# RGB_LEDs.net
KiCad netlist of a schematic drawn in Altium Designer
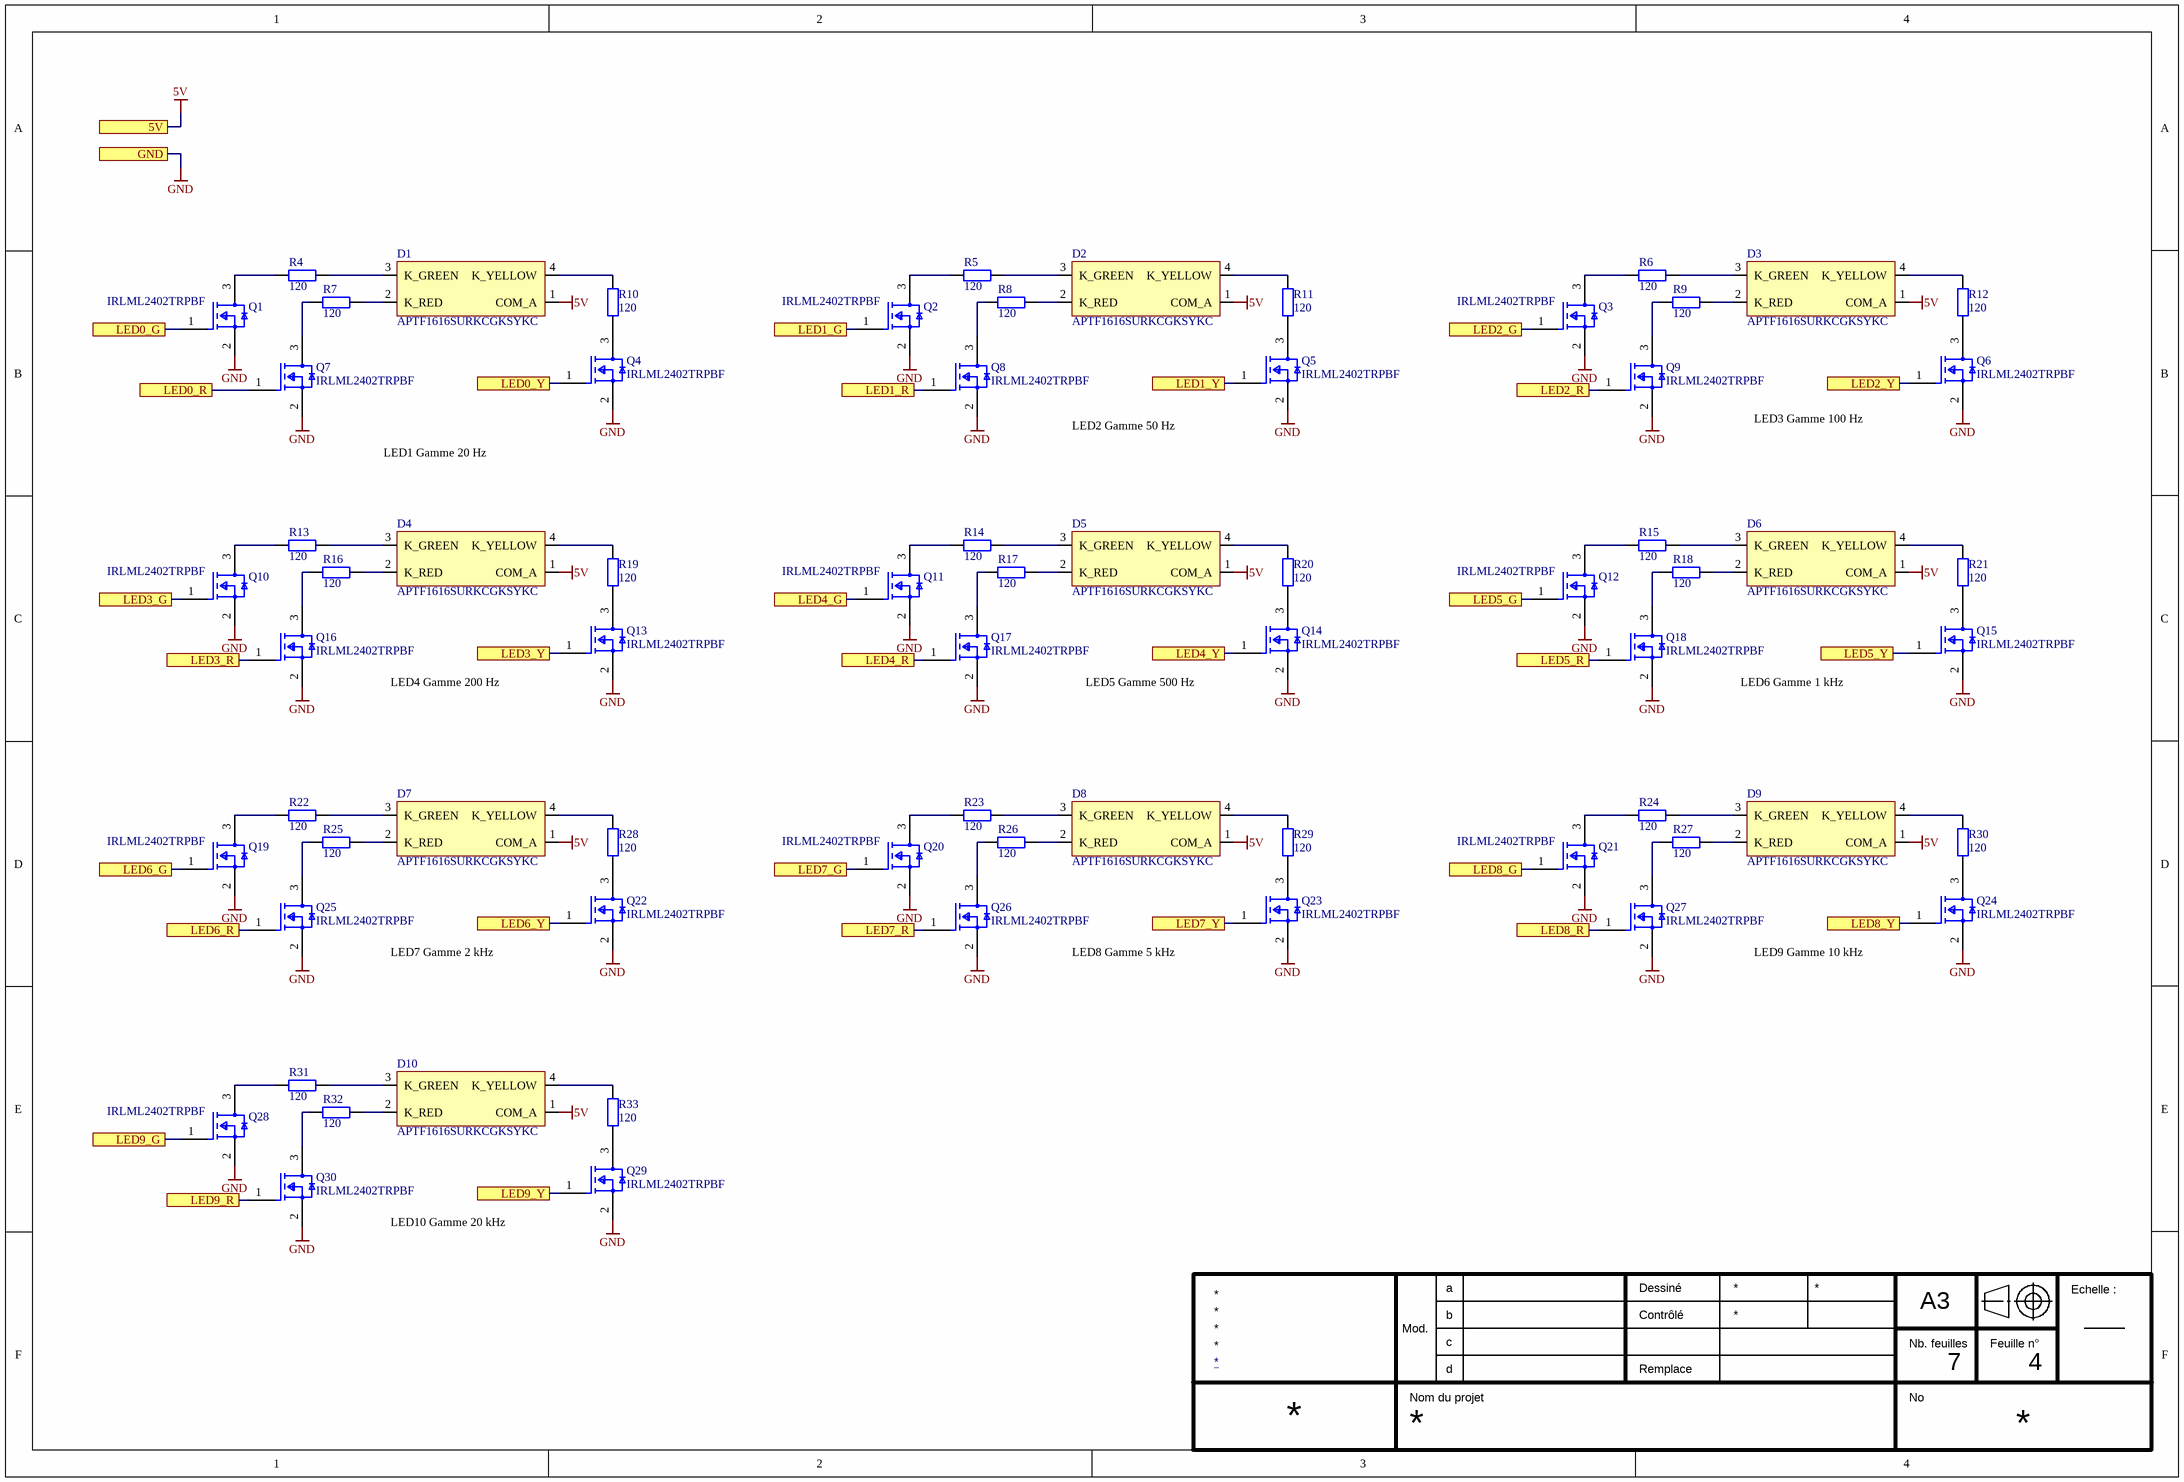
[diagram p0: RGB_LEDs.SchDoc]

(export (version "E")
  (design (tool "Eeschema 10.0.6"))
  (components
    (comp (ref "D1")
      (value "APTF1616SURKCGKSYKC")
      (footprint "APTF1616SURKCGKSYKC")
      (fields (field (name "MOUSER PART NUMBER") "604-APTF1616KCGKSYKC"))
      (libsource (lib "2225B_VumetreFrequenciel") (part "APTF1616SURKCGKSYKC"))
    )
    (comp (ref "D2")
      (value "APTF1616SURKCGKSYKC")
      (footprint "APTF1616SURKCGKSYKC")
      (fields (field (name "MOUSER PART NUMBER") "604-APTF1616KCGKSYKC"))
      (libsource (lib "2225B_VumetreFrequenciel") (part "APTF1616SURKCGKSYKC"))
    )
    (comp (ref "D3")
      (value "APTF1616SURKCGKSYKC")
      (footprint "APTF1616SURKCGKSYKC")
      (fields (field (name "MOUSER PART NUMBER") "604-APTF1616KCGKSYKC"))
      (libsource (lib "2225B_VumetreFrequenciel") (part "APTF1616SURKCGKSYKC"))
    )
    (comp (ref "D4")
      (value "APTF1616SURKCGKSYKC")
      (footprint "APTF1616SURKCGKSYKC")
      (fields (field (name "MOUSER PART NUMBER") "604-APTF1616KCGKSYKC"))
      (libsource (lib "2225B_VumetreFrequenciel") (part "APTF1616SURKCGKSYKC"))
    )
    (comp (ref "D5")
      (value "APTF1616SURKCGKSYKC")
      (footprint "APTF1616SURKCGKSYKC")
      (fields (field (name "MOUSER PART NUMBER") "604-APTF1616KCGKSYKC"))
      (libsource (lib "2225B_VumetreFrequenciel") (part "APTF1616SURKCGKSYKC"))
    )
    (comp (ref "D6")
      (value "APTF1616SURKCGKSYKC")
      (footprint "APTF1616SURKCGKSYKC")
      (fields (field (name "MOUSER PART NUMBER") "604-APTF1616KCGKSYKC"))
      (libsource (lib "2225B_VumetreFrequenciel") (part "APTF1616SURKCGKSYKC"))
    )
    (comp (ref "D7")
      (value "APTF1616SURKCGKSYKC")
      (footprint "APTF1616SURKCGKSYKC")
      (fields (field (name "MOUSER PART NUMBER") "604-APTF1616KCGKSYKC"))
      (libsource (lib "2225B_VumetreFrequenciel") (part "APTF1616SURKCGKSYKC"))
    )
    (comp (ref "D8")
      (value "APTF1616SURKCGKSYKC")
      (footprint "APTF1616SURKCGKSYKC")
      (fields (field (name "MOUSER PART NUMBER") "604-APTF1616KCGKSYKC"))
      (libsource (lib "2225B_VumetreFrequenciel") (part "APTF1616SURKCGKSYKC"))
    )
    (comp (ref "D9")
      (value "APTF1616SURKCGKSYKC")
      (footprint "APTF1616SURKCGKSYKC")
      (fields (field (name "MOUSER PART NUMBER") "604-APTF1616KCGKSYKC"))
      (libsource (lib "2225B_VumetreFrequenciel") (part "APTF1616SURKCGKSYKC"))
    )
    (comp (ref "D10")
      (value "APTF1616SURKCGKSYKC")
      (footprint "APTF1616SURKCGKSYKC")
      (fields (field (name "MOUSER PART NUMBER") "604-APTF1616KCGKSYKC"))
      (libsource (lib "2225B_VumetreFrequenciel") (part "APTF1616SURKCGKSYKC"))
    )
    (comp (ref "Q1")
      (value "IRLML2402TRPBF")
      (footprint "FP-Micro3-IPC_B")
      (description "MOSFET N-CH 20V 1.2A SOT-23")
      (libsource (lib "Altium Content Vault") (part "0a9ea7c96deaaede766a5b531c28de0"))
    )
    (comp (ref "Q2")
      (value "IRLML2402TRPBF")
      (footprint "FP-Micro3-IPC_B")
      (description "MOSFET N-CH 20V 1.2A SOT-23")
      (libsource (lib "Altium Content Vault") (part "0a9ea7c96deaaede766a5b531c28de0"))
    )
    (comp (ref "Q3")
      (value "IRLML2402TRPBF")
      (footprint "FP-Micro3-IPC_B")
      (description "MOSFET N-CH 20V 1.2A SOT-23")
      (libsource (lib "Altium Content Vault") (part "0a9ea7c96deaaede766a5b531c28de0"))
    )
    (comp (ref "Q4")
      (value "IRLML2402TRPBF")
      (footprint "FP-Micro3-IPC_B")
      (description "MOSFET N-CH 20V 1.2A SOT-23")
      (libsource (lib "Altium Content Vault") (part "0a9ea7c96deaaede766a5b531c28de0"))
    )
    (comp (ref "Q5")
      (value "IRLML2402TRPBF")
      (footprint "FP-Micro3-IPC_B")
      (description "MOSFET N-CH 20V 1.2A SOT-23")
      (libsource (lib "Altium Content Vault") (part "0a9ea7c96deaaede766a5b531c28de0"))
    )
    (comp (ref "Q6")
      (value "IRLML2402TRPBF")
      (footprint "FP-Micro3-IPC_B")
      (description "MOSFET N-CH 20V 1.2A SOT-23")
      (libsource (lib "Altium Content Vault") (part "0a9ea7c96deaaede766a5b531c28de0"))
    )
    (comp (ref "Q7")
      (value "IRLML2402TRPBF")
      (footprint "FP-Micro3-IPC_B")
      (description "MOSFET N-CH 20V 1.2A SOT-23")
      (libsource (lib "Altium Content Vault") (part "0a9ea7c96deaaede766a5b531c28de0"))
    )
    (comp (ref "Q8")
      (value "IRLML2402TRPBF")
      (footprint "FP-Micro3-IPC_B")
      (description "MOSFET N-CH 20V 1.2A SOT-23")
      (libsource (lib "Altium Content Vault") (part "0a9ea7c96deaaede766a5b531c28de0"))
    )
    (comp (ref "Q9")
      (value "IRLML2402TRPBF")
      (footprint "FP-Micro3-IPC_B")
      (description "MOSFET N-CH 20V 1.2A SOT-23")
      (libsource (lib "Altium Content Vault") (part "0a9ea7c96deaaede766a5b531c28de0"))
    )
    (comp (ref "Q10")
      (value "IRLML2402TRPBF")
      (footprint "FP-Micro3-IPC_B")
      (description "MOSFET N-CH 20V 1.2A SOT-23")
      (libsource (lib "Altium Content Vault") (part "0a9ea7c96deaaede766a5b531c28de0"))
    )
    (comp (ref "Q11")
      (value "IRLML2402TRPBF")
      (footprint "FP-Micro3-IPC_B")
      (description "MOSFET N-CH 20V 1.2A SOT-23")
      (libsource (lib "Altium Content Vault") (part "0a9ea7c96deaaede766a5b531c28de0"))
    )
    (comp (ref "Q12")
      (value "IRLML2402TRPBF")
      (footprint "FP-Micro3-IPC_B")
      (description "MOSFET N-CH 20V 1.2A SOT-23")
      (libsource (lib "Altium Content Vault") (part "0a9ea7c96deaaede766a5b531c28de0"))
    )
    (comp (ref "Q13")
      (value "IRLML2402TRPBF")
      (footprint "FP-Micro3-IPC_B")
      (description "MOSFET N-CH 20V 1.2A SOT-23")
      (libsource (lib "Altium Content Vault") (part "0a9ea7c96deaaede766a5b531c28de0"))
    )
    (comp (ref "Q14")
      (value "IRLML2402TRPBF")
      (footprint "FP-Micro3-IPC_B")
      (description "MOSFET N-CH 20V 1.2A SOT-23")
      (libsource (lib "Altium Content Vault") (part "0a9ea7c96deaaede766a5b531c28de0"))
    )
    (comp (ref "Q15")
      (value "IRLML2402TRPBF")
      (footprint "FP-Micro3-IPC_B")
      (description "MOSFET N-CH 20V 1.2A SOT-23")
      (libsource (lib "Altium Content Vault") (part "0a9ea7c96deaaede766a5b531c28de0"))
    )
    (comp (ref "Q16")
      (value "IRLML2402TRPBF")
      (footprint "FP-Micro3-IPC_B")
      (description "MOSFET N-CH 20V 1.2A SOT-23")
      (libsource (lib "Altium Content Vault") (part "0a9ea7c96deaaede766a5b531c28de0"))
    )
    (comp (ref "Q17")
      (value "IRLML2402TRPBF")
      (footprint "FP-Micro3-IPC_B")
      (description "MOSFET N-CH 20V 1.2A SOT-23")
      (libsource (lib "Altium Content Vault") (part "0a9ea7c96deaaede766a5b531c28de0"))
    )
    (comp (ref "Q18")
      (value "IRLML2402TRPBF")
      (footprint "FP-Micro3-IPC_B")
      (description "MOSFET N-CH 20V 1.2A SOT-23")
      (libsource (lib "Altium Content Vault") (part "0a9ea7c96deaaede766a5b531c28de0"))
    )
    (comp (ref "Q19")
      (value "IRLML2402TRPBF")
      (footprint "FP-Micro3-IPC_B")
      (description "MOSFET N-CH 20V 1.2A SOT-23")
      (libsource (lib "Altium Content Vault") (part "0a9ea7c96deaaede766a5b531c28de0"))
    )
    (comp (ref "Q20")
      (value "IRLML2402TRPBF")
      (footprint "FP-Micro3-IPC_B")
      (description "MOSFET N-CH 20V 1.2A SOT-23")
      (libsource (lib "Altium Content Vault") (part "0a9ea7c96deaaede766a5b531c28de0"))
    )
    (comp (ref "Q21")
      (value "IRLML2402TRPBF")
      (footprint "FP-Micro3-IPC_B")
      (description "MOSFET N-CH 20V 1.2A SOT-23")
      (libsource (lib "Altium Content Vault") (part "0a9ea7c96deaaede766a5b531c28de0"))
    )
    (comp (ref "Q22")
      (value "IRLML2402TRPBF")
      (footprint "FP-Micro3-IPC_B")
      (description "MOSFET N-CH 20V 1.2A SOT-23")
      (libsource (lib "Altium Content Vault") (part "0a9ea7c96deaaede766a5b531c28de0"))
    )
    (comp (ref "Q23")
      (value "IRLML2402TRPBF")
      (footprint "FP-Micro3-IPC_B")
      (description "MOSFET N-CH 20V 1.2A SOT-23")
      (libsource (lib "Altium Content Vault") (part "0a9ea7c96deaaede766a5b531c28de0"))
    )
    (comp (ref "Q24")
      (value "IRLML2402TRPBF")
      (footprint "FP-Micro3-IPC_B")
      (description "MOSFET N-CH 20V 1.2A SOT-23")
      (libsource (lib "Altium Content Vault") (part "0a9ea7c96deaaede766a5b531c28de0"))
    )
    (comp (ref "Q25")
      (value "IRLML2402TRPBF")
      (footprint "FP-Micro3-IPC_B")
      (description "MOSFET N-CH 20V 1.2A SOT-23")
      (libsource (lib "Altium Content Vault") (part "0a9ea7c96deaaede766a5b531c28de0"))
    )
    (comp (ref "Q26")
      (value "IRLML2402TRPBF")
      (footprint "FP-Micro3-IPC_B")
      (description "MOSFET N-CH 20V 1.2A SOT-23")
      (libsource (lib "Altium Content Vault") (part "0a9ea7c96deaaede766a5b531c28de0"))
    )
    (comp (ref "Q27")
      (value "IRLML2402TRPBF")
      (footprint "FP-Micro3-IPC_B")
      (description "MOSFET N-CH 20V 1.2A SOT-23")
      (libsource (lib "Altium Content Vault") (part "0a9ea7c96deaaede766a5b531c28de0"))
    )
    (comp (ref "Q28")
      (value "IRLML2402TRPBF")
      (footprint "FP-Micro3-IPC_B")
      (description "MOSFET N-CH 20V 1.2A SOT-23")
      (libsource (lib "Altium Content Vault") (part "0a9ea7c96deaaede766a5b531c28de0"))
    )
    (comp (ref "Q29")
      (value "IRLML2402TRPBF")
      (footprint "FP-Micro3-IPC_B")
      (description "MOSFET N-CH 20V 1.2A SOT-23")
      (libsource (lib "Altium Content Vault") (part "0a9ea7c96deaaede766a5b531c28de0"))
    )
    (comp (ref "Q30")
      (value "IRLML2402TRPBF")
      (footprint "FP-Micro3-IPC_B")
      (description "MOSFET N-CH 20V 1.2A SOT-23")
      (libsource (lib "Altium Content Vault") (part "0a9ea7c96deaaede766a5b531c28de0"))
    )
    (comp (ref "R4")
      (value "120")
      (footprint "RESC2012X06M")
      (description "Resistor")
      (fields (field (name "PUBLISHER") "Altium Limited"))
      (libsource (lib "") (part "Res2_1"))
    )
    (comp (ref "R5")
      (value "120")
      (footprint "RESC2012X06M")
      (description "Resistor")
      (fields (field (name "PUBLISHER") "Altium Limited"))
      (libsource (lib "") (part "Res2_1"))
    )
    (comp (ref "R6")
      (value "120")
      (footprint "RESC2012X06M")
      (description "Resistor")
      (fields (field (name "PUBLISHER") "Altium Limited"))
      (libsource (lib "") (part "Res2_1"))
    )
    (comp (ref "R7")
      (value "120")
      (footprint "RESC2012X06M")
      (description "Resistor")
      (fields (field (name "PUBLISHER") "Altium Limited"))
      (libsource (lib "") (part "Res2_1"))
    )
    (comp (ref "R8")
      (value "120")
      (footprint "RESC2012X06M")
      (description "Resistor")
      (fields (field (name "PUBLISHER") "Altium Limited"))
      (libsource (lib "") (part "Res2_1"))
    )
    (comp (ref "R9")
      (value "120")
      (footprint "RESC2012X06M")
      (description "Resistor")
      (fields (field (name "PUBLISHER") "Altium Limited"))
      (libsource (lib "") (part "Res2_1"))
    )
    (comp (ref "R10")
      (value "120")
      (footprint "RESC2012X06M")
      (description "Resistor")
      (fields (field (name "PUBLISHER") "Altium Limited"))
      (libsource (lib "Miscellaneous Devices") (part "Res2"))
    )
    (comp (ref "R11")
      (value "120")
      (footprint "RESC2012X06M")
      (description "Resistor")
      (fields (field (name "PUBLISHER") "Altium Limited"))
      (libsource (lib "Miscellaneous Devices") (part "Res2"))
    )
    (comp (ref "R12")
      (value "120")
      (footprint "RESC2012X06M")
      (description "Resistor")
      (fields (field (name "PUBLISHER") "Altium Limited"))
      (libsource (lib "Miscellaneous Devices") (part "Res2"))
    )
    (comp (ref "R13")
      (value "120")
      (footprint "RESC2012X06M")
      (description "Resistor")
      (fields (field (name "PUBLISHER") "Altium Limited"))
      (libsource (lib "") (part "Res2_1"))
    )
    (comp (ref "R14")
      (value "120")
      (footprint "RESC2012X06M")
      (description "Resistor")
      (fields (field (name "PUBLISHER") "Altium Limited"))
      (libsource (lib "") (part "Res2_1"))
    )
    (comp (ref "R15")
      (value "120")
      (footprint "RESC2012X06M")
      (description "Resistor")
      (fields (field (name "PUBLISHER") "Altium Limited"))
      (libsource (lib "") (part "Res2_1"))
    )
    (comp (ref "R16")
      (value "120")
      (footprint "RESC2012X06M")
      (description "Resistor")
      (fields (field (name "PUBLISHER") "Altium Limited"))
      (libsource (lib "") (part "Res2_1"))
    )
    (comp (ref "R17")
      (value "120")
      (footprint "RESC2012X06M")
      (description "Resistor")
      (fields (field (name "PUBLISHER") "Altium Limited"))
      (libsource (lib "") (part "Res2_1"))
    )
    (comp (ref "R18")
      (value "120")
      (footprint "RESC2012X06M")
      (description "Resistor")
      (fields (field (name "PUBLISHER") "Altium Limited"))
      (libsource (lib "") (part "Res2_1"))
    )
    (comp (ref "R19")
      (value "120")
      (footprint "RESC2012X06M")
      (description "Resistor")
      (fields (field (name "PUBLISHER") "Altium Limited"))
      (libsource (lib "Miscellaneous Devices") (part "Res2"))
    )
    (comp (ref "R20")
      (value "120")
      (footprint "RESC2012X06M")
      (description "Resistor")
      (fields (field (name "PUBLISHER") "Altium Limited"))
      (libsource (lib "Miscellaneous Devices") (part "Res2"))
    )
    (comp (ref "R21")
      (value "120")
      (footprint "RESC2012X06M")
      (description "Resistor")
      (fields (field (name "PUBLISHER") "Altium Limited"))
      (libsource (lib "Miscellaneous Devices") (part "Res2"))
    )
    (comp (ref "R22")
      (value "120")
      (footprint "RESC2012X06M")
      (description "Resistor")
      (fields (field (name "PUBLISHER") "Altium Limited"))
      (libsource (lib "") (part "Res2_1"))
    )
    (comp (ref "R23")
      (value "120")
      (footprint "RESC2012X06M")
      (description "Resistor")
      (fields (field (name "PUBLISHER") "Altium Limited"))
      (libsource (lib "") (part "Res2_1"))
    )
    (comp (ref "R24")
      (value "120")
      (footprint "RESC2012X06M")
      (description "Resistor")
      (fields (field (name "PUBLISHER") "Altium Limited"))
      (libsource (lib "") (part "Res2_1"))
    )
    (comp (ref "R25")
      (value "120")
      (footprint "RESC2012X06M")
      (description "Resistor")
      (fields (field (name "PUBLISHER") "Altium Limited"))
      (libsource (lib "") (part "Res2_1"))
    )
    (comp (ref "R26")
      (value "120")
      (footprint "RESC2012X06M")
      (description "Resistor")
      (fields (field (name "PUBLISHER") "Altium Limited"))
      (libsource (lib "") (part "Res2_1"))
    )
    (comp (ref "R27")
      (value "120")
      (footprint "RESC2012X06M")
      (description "Resistor")
      (fields (field (name "PUBLISHER") "Altium Limited"))
      (libsource (lib "") (part "Res2_1"))
    )
    (comp (ref "R28")
      (value "120")
      (footprint "RESC2012X06M")
      (description "Resistor")
      (fields (field (name "PUBLISHER") "Altium Limited"))
      (libsource (lib "Miscellaneous Devices") (part "Res2"))
    )
    (comp (ref "R29")
      (value "120")
      (footprint "RESC2012X06M")
      (description "Resistor")
      (fields (field (name "PUBLISHER") "Altium Limited"))
      (libsource (lib "Miscellaneous Devices") (part "Res2"))
    )
    (comp (ref "R30")
      (value "120")
      (footprint "RESC2012X06M")
      (description "Resistor")
      (fields (field (name "PUBLISHER") "Altium Limited"))
      (libsource (lib "Miscellaneous Devices") (part "Res2"))
    )
    (comp (ref "R31")
      (value "120")
      (footprint "RESC2012X06M")
      (description "Resistor")
      (fields (field (name "PUBLISHER") "Altium Limited"))
      (libsource (lib "") (part "Res2_1"))
    )
    (comp (ref "R32")
      (value "120")
      (footprint "RESC2012X06M")
      (description "Resistor")
      (fields (field (name "PUBLISHER") "Altium Limited"))
      (libsource (lib "") (part "Res2_1"))
    )
    (comp (ref "R33")
      (value "120")
      (footprint "RESC2012X06M")
      (description "Resistor")
      (fields (field (name "PUBLISHER") "Altium Limited"))
      (libsource (lib "Miscellaneous Devices") (part "Res2"))
    )
  )
  (nets
    (net (code "1") (name "/LED0_G") (class "Default")
      (node (ref "Q1") (pin "1") (pinfunction "G_1") (pintype "passive"))
    )
    (net (code "2") (name "/LED0_R") (class "Default")
      (node (ref "Q7") (pin "1") (pinfunction "G_1") (pintype "passive"))
    )
    (net (code "3") (name "/LED0_Y") (class "Default")
      (node (ref "Q4") (pin "1") (pinfunction "G_1") (pintype "passive"))
    )
    (net (code "4") (name "/LED1_G") (class "Default")
      (node (ref "Q2") (pin "1") (pinfunction "G_1") (pintype "passive"))
    )
    (net (code "5") (name "/LED1_R") (class "Default")
      (node (ref "Q8") (pin "1") (pinfunction "G_1") (pintype "passive"))
    )
    (net (code "6") (name "/LED1_Y") (class "Default")
      (node (ref "Q5") (pin "1") (pinfunction "G_1") (pintype "passive"))
    )
    (net (code "7") (name "/LED2_G") (class "Default")
      (node (ref "Q3") (pin "1") (pinfunction "G_1") (pintype "passive"))
    )
    (net (code "8") (name "/LED2_R") (class "Default")
      (node (ref "Q9") (pin "1") (pinfunction "G_1") (pintype "passive"))
    )
    (net (code "9") (name "/LED2_Y") (class "Default")
      (node (ref "Q6") (pin "1") (pinfunction "G_1") (pintype "passive"))
    )
    (net (code "10") (name "/LED3_G") (class "Default")
      (node (ref "Q10") (pin "1") (pinfunction "G_1") (pintype "passive"))
    )
    (net (code "11") (name "/LED3_R") (class "Default")
      (node (ref "Q16") (pin "1") (pinfunction "G_1") (pintype "passive"))
    )
    (net (code "12") (name "/LED3_Y") (class "Default")
      (node (ref "Q13") (pin "1") (pinfunction "G_1") (pintype "passive"))
    )
    (net (code "13") (name "/LED4_G") (class "Default")
      (node (ref "Q11") (pin "1") (pinfunction "G_1") (pintype "passive"))
    )
    (net (code "14") (name "/LED4_R") (class "Default")
      (node (ref "Q17") (pin "1") (pinfunction "G_1") (pintype "passive"))
    )
    (net (code "15") (name "/LED4_Y") (class "Default")
      (node (ref "Q14") (pin "1") (pinfunction "G_1") (pintype "passive"))
    )
    (net (code "16") (name "/LED5_G") (class "Default")
      (node (ref "Q12") (pin "1") (pinfunction "G_1") (pintype "passive"))
    )
    (net (code "17") (name "/LED5_R") (class "Default")
      (node (ref "Q18") (pin "1") (pinfunction "G_1") (pintype "passive"))
    )
    (net (code "18") (name "/LED5_Y") (class "Default")
      (node (ref "Q15") (pin "1") (pinfunction "G_1") (pintype "passive"))
    )
    (net (code "19") (name "/LED6_G") (class "Default")
      (node (ref "Q19") (pin "1") (pinfunction "G_1") (pintype "passive"))
    )
    (net (code "20") (name "/LED6_R") (class "Default")
      (node (ref "Q25") (pin "1") (pinfunction "G_1") (pintype "passive"))
    )
    (net (code "21") (name "/LED6_Y") (class "Default")
      (node (ref "Q22") (pin "1") (pinfunction "G_1") (pintype "passive"))
    )
    (net (code "22") (name "/LED7_G") (class "Default")
      (node (ref "Q20") (pin "1") (pinfunction "G_1") (pintype "passive"))
    )
    (net (code "23") (name "/LED7_R") (class "Default")
      (node (ref "Q26") (pin "1") (pinfunction "G_1") (pintype "passive"))
    )
    (net (code "24") (name "/LED7_Y") (class "Default")
      (node (ref "Q23") (pin "1") (pinfunction "G_1") (pintype "passive"))
    )
    (net (code "25") (name "/LED8_G") (class "Default")
      (node (ref "Q21") (pin "1") (pinfunction "G_1") (pintype "passive"))
    )
    (net (code "26") (name "/LED8_R") (class "Default")
      (node (ref "Q27") (pin "1") (pinfunction "G_1") (pintype "passive"))
    )
    (net (code "27") (name "/LED8_Y") (class "Default")
      (node (ref "Q24") (pin "1") (pinfunction "G_1") (pintype "passive"))
    )
    (net (code "28") (name "/LED9_G") (class "Default")
      (node (ref "Q28") (pin "1") (pinfunction "G_1") (pintype "passive"))
    )
    (net (code "29") (name "/LED9_R") (class "Default")
      (node (ref "Q30") (pin "1") (pinfunction "G_1") (pintype "passive"))
    )
    (net (code "30") (name "/LED9_Y") (class "Default")
      (node (ref "Q29") (pin "1") (pinfunction "G_1") (pintype "passive"))
    )
    (net (code "31") (name "5V") (class "Default")
      (node (ref "D1") (pin "1") (pinfunction "COM_A_1") (pintype "passive"))
      (node (ref "D10") (pin "1") (pinfunction "COM_A_1") (pintype "passive"))
      (node (ref "D2") (pin "1") (pinfunction "COM_A_1") (pintype "passive"))
      (node (ref "D3") (pin "1") (pinfunction "COM_A_1") (pintype "passive"))
      (node (ref "D4") (pin "1") (pinfunction "COM_A_1") (pintype "passive"))
      (node (ref "D5") (pin "1") (pinfunction "COM_A_1") (pintype "passive"))
      (node (ref "D6") (pin "1") (pinfunction "COM_A_1") (pintype "passive"))
      (node (ref "D7") (pin "1") (pinfunction "COM_A_1") (pintype "passive"))
      (node (ref "D8") (pin "1") (pinfunction "COM_A_1") (pintype "passive"))
      (node (ref "D9") (pin "1") (pinfunction "COM_A_1") (pintype "passive"))
    )
    (net (code "32") (name "GND") (class "Default")
      (node (ref "Q1") (pin "2") (pinfunction "S_2") (pintype "passive"))
      (node (ref "Q10") (pin "2") (pinfunction "S_2") (pintype "passive"))
      (node (ref "Q11") (pin "2") (pinfunction "S_2") (pintype "passive"))
      (node (ref "Q12") (pin "2") (pinfunction "S_2") (pintype "passive"))
      (node (ref "Q13") (pin "2") (pinfunction "S_2") (pintype "passive"))
      (node (ref "Q14") (pin "2") (pinfunction "S_2") (pintype "passive"))
      (node (ref "Q15") (pin "2") (pinfunction "S_2") (pintype "passive"))
      (node (ref "Q16") (pin "2") (pinfunction "S_2") (pintype "passive"))
      (node (ref "Q17") (pin "2") (pinfunction "S_2") (pintype "passive"))
      (node (ref "Q18") (pin "2") (pinfunction "S_2") (pintype "passive"))
      (node (ref "Q19") (pin "2") (pinfunction "S_2") (pintype "passive"))
      (node (ref "Q2") (pin "2") (pinfunction "S_2") (pintype "passive"))
      (node (ref "Q20") (pin "2") (pinfunction "S_2") (pintype "passive"))
      (node (ref "Q21") (pin "2") (pinfunction "S_2") (pintype "passive"))
      (node (ref "Q22") (pin "2") (pinfunction "S_2") (pintype "passive"))
      (node (ref "Q23") (pin "2") (pinfunction "S_2") (pintype "passive"))
      (node (ref "Q24") (pin "2") (pinfunction "S_2") (pintype "passive"))
      (node (ref "Q25") (pin "2") (pinfunction "S_2") (pintype "passive"))
      (node (ref "Q26") (pin "2") (pinfunction "S_2") (pintype "passive"))
      (node (ref "Q27") (pin "2") (pinfunction "S_2") (pintype "passive"))
      (node (ref "Q28") (pin "2") (pinfunction "S_2") (pintype "passive"))
      (node (ref "Q29") (pin "2") (pinfunction "S_2") (pintype "passive"))
      (node (ref "Q3") (pin "2") (pinfunction "S_2") (pintype "passive"))
      (node (ref "Q30") (pin "2") (pinfunction "S_2") (pintype "passive"))
      (node (ref "Q4") (pin "2") (pinfunction "S_2") (pintype "passive"))
      (node (ref "Q5") (pin "2") (pinfunction "S_2") (pintype "passive"))
      (node (ref "Q6") (pin "2") (pinfunction "S_2") (pintype "passive"))
      (node (ref "Q7") (pin "2") (pinfunction "S_2") (pintype "passive"))
      (node (ref "Q8") (pin "2") (pinfunction "S_2") (pintype "passive"))
      (node (ref "Q9") (pin "2") (pinfunction "S_2") (pintype "passive"))
    )
    (net (code "33") (name "Net-(D1-K_GREEN)") (class "Default")
      (node (ref "D1") (pin "3") (pinfunction "K_GREEN_3") (pintype "passive"))
      (node (ref "R4") (pin "1") (pinfunction "1_1") (pintype "passive"))
    )
    (net (code "34") (name "Net-(D1-K_RED)") (class "Default")
      (node (ref "D1") (pin "2") (pinfunction "K_RED_2") (pintype "passive"))
      (node (ref "R7") (pin "1") (pinfunction "1_1") (pintype "passive"))
    )
    (net (code "35") (name "Net-(D1-K_YELLOW)") (class "Default")
      (node (ref "D1") (pin "4") (pinfunction "K_YELLOW_4") (pintype "passive"))
      (node (ref "R10") (pin "1") (pinfunction "1_1") (pintype "passive"))
    )
    (net (code "36") (name "Net-(D2-K_GREEN)") (class "Default")
      (node (ref "D2") (pin "3") (pinfunction "K_GREEN_3") (pintype "passive"))
      (node (ref "R5") (pin "1") (pinfunction "1_1") (pintype "passive"))
    )
    (net (code "37") (name "Net-(D2-K_RED)") (class "Default")
      (node (ref "D2") (pin "2") (pinfunction "K_RED_2") (pintype "passive"))
      (node (ref "R8") (pin "1") (pinfunction "1_1") (pintype "passive"))
    )
    (net (code "38") (name "Net-(D2-K_YELLOW)") (class "Default")
      (node (ref "D2") (pin "4") (pinfunction "K_YELLOW_4") (pintype "passive"))
      (node (ref "R11") (pin "1") (pinfunction "1_1") (pintype "passive"))
    )
    (net (code "39") (name "Net-(D3-K_GREEN)") (class "Default")
      (node (ref "D3") (pin "3") (pinfunction "K_GREEN_3") (pintype "passive"))
      (node (ref "R6") (pin "1") (pinfunction "1_1") (pintype "passive"))
    )
    (net (code "40") (name "Net-(D3-K_RED)") (class "Default")
      (node (ref "D3") (pin "2") (pinfunction "K_RED_2") (pintype "passive"))
      (node (ref "R9") (pin "1") (pinfunction "1_1") (pintype "passive"))
    )
    (net (code "41") (name "Net-(D3-K_YELLOW)") (class "Default")
      (node (ref "D3") (pin "4") (pinfunction "K_YELLOW_4") (pintype "passive"))
      (node (ref "R12") (pin "1") (pinfunction "1_1") (pintype "passive"))
    )
    (net (code "42") (name "Net-(D4-K_GREEN)") (class "Default")
      (node (ref "D4") (pin "3") (pinfunction "K_GREEN_3") (pintype "passive"))
      (node (ref "R13") (pin "1") (pinfunction "1_1") (pintype "passive"))
    )
    (net (code "43") (name "Net-(D4-K_RED)") (class "Default")
      (node (ref "D4") (pin "2") (pinfunction "K_RED_2") (pintype "passive"))
      (node (ref "R16") (pin "1") (pinfunction "1_1") (pintype "passive"))
    )
    (net (code "44") (name "Net-(D4-K_YELLOW)") (class "Default")
      (node (ref "D4") (pin "4") (pinfunction "K_YELLOW_4") (pintype "passive"))
      (node (ref "R19") (pin "1") (pinfunction "1_1") (pintype "passive"))
    )
    (net (code "45") (name "Net-(D5-K_GREEN)") (class "Default")
      (node (ref "D5") (pin "3") (pinfunction "K_GREEN_3") (pintype "passive"))
      (node (ref "R14") (pin "1") (pinfunction "1_1") (pintype "passive"))
    )
    (net (code "46") (name "Net-(D5-K_RED)") (class "Default")
      (node (ref "D5") (pin "2") (pinfunction "K_RED_2") (pintype "passive"))
      (node (ref "R17") (pin "1") (pinfunction "1_1") (pintype "passive"))
    )
    (net (code "47") (name "Net-(D5-K_YELLOW)") (class "Default")
      (node (ref "D5") (pin "4") (pinfunction "K_YELLOW_4") (pintype "passive"))
      (node (ref "R20") (pin "1") (pinfunction "1_1") (pintype "passive"))
    )
    (net (code "48") (name "Net-(D6-K_GREEN)") (class "Default")
      (node (ref "D6") (pin "3") (pinfunction "K_GREEN_3") (pintype "passive"))
      (node (ref "R15") (pin "1") (pinfunction "1_1") (pintype "passive"))
    )
    (net (code "49") (name "Net-(D6-K_RED)") (class "Default")
      (node (ref "D6") (pin "2") (pinfunction "K_RED_2") (pintype "passive"))
      (node (ref "R18") (pin "1") (pinfunction "1_1") (pintype "passive"))
    )
    (net (code "50") (name "Net-(D6-K_YELLOW)") (class "Default")
      (node (ref "D6") (pin "4") (pinfunction "K_YELLOW_4") (pintype "passive"))
      (node (ref "R21") (pin "1") (pinfunction "1_1") (pintype "passive"))
    )
    (net (code "51") (name "Net-(D7-K_GREEN)") (class "Default")
      (node (ref "D7") (pin "3") (pinfunction "K_GREEN_3") (pintype "passive"))
      (node (ref "R22") (pin "1") (pinfunction "1_1") (pintype "passive"))
    )
    (net (code "52") (name "Net-(D7-K_RED)") (class "Default")
      (node (ref "D7") (pin "2") (pinfunction "K_RED_2") (pintype "passive"))
      (node (ref "R25") (pin "1") (pinfunction "1_1") (pintype "passive"))
    )
    (net (code "53") (name "Net-(D7-K_YELLOW)") (class "Default")
      (node (ref "D7") (pin "4") (pinfunction "K_YELLOW_4") (pintype "passive"))
      (node (ref "R28") (pin "1") (pinfunction "1_1") (pintype "passive"))
    )
    (net (code "54") (name "Net-(D8-K_GREEN)") (class "Default")
      (node (ref "D8") (pin "3") (pinfunction "K_GREEN_3") (pintype "passive"))
      (node (ref "R23") (pin "1") (pinfunction "1_1") (pintype "passive"))
    )
    (net (code "55") (name "Net-(D8-K_RED)") (class "Default")
      (node (ref "D8") (pin "2") (pinfunction "K_RED_2") (pintype "passive"))
      (node (ref "R26") (pin "1") (pinfunction "1_1") (pintype "passive"))
    )
    (net (code "56") (name "Net-(D8-K_YELLOW)") (class "Default")
      (node (ref "D8") (pin "4") (pinfunction "K_YELLOW_4") (pintype "passive"))
      (node (ref "R29") (pin "1") (pinfunction "1_1") (pintype "passive"))
    )
    (net (code "57") (name "Net-(D9-K_GREEN)") (class "Default")
      (node (ref "D9") (pin "3") (pinfunction "K_GREEN_3") (pintype "passive"))
      (node (ref "R24") (pin "1") (pinfunction "1_1") (pintype "passive"))
    )
    (net (code "58") (name "Net-(D9-K_RED)") (class "Default")
      (node (ref "D9") (pin "2") (pinfunction "K_RED_2") (pintype "passive"))
      (node (ref "R27") (pin "1") (pinfunction "1_1") (pintype "passive"))
    )
    (net (code "59") (name "Net-(D9-K_YELLOW)") (class "Default")
      (node (ref "D9") (pin "4") (pinfunction "K_YELLOW_4") (pintype "passive"))
      (node (ref "R30") (pin "1") (pinfunction "1_1") (pintype "passive"))
    )
    (net (code "60") (name "Net-(D10-K_GREEN)") (class "Default")
      (node (ref "D10") (pin "3") (pinfunction "K_GREEN_3") (pintype "passive"))
      (node (ref "R31") (pin "1") (pinfunction "1_1") (pintype "passive"))
    )
    (net (code "61") (name "Net-(D10-K_RED)") (class "Default")
      (node (ref "D10") (pin "2") (pinfunction "K_RED_2") (pintype "passive"))
      (node (ref "R32") (pin "1") (pinfunction "1_1") (pintype "passive"))
    )
    (net (code "62") (name "Net-(D10-K_YELLOW)") (class "Default")
      (node (ref "D10") (pin "4") (pinfunction "K_YELLOW_4") (pintype "passive"))
      (node (ref "R33") (pin "1") (pinfunction "1_1") (pintype "passive"))
    )
    (net (code "63") (name "Net-(Q1-D)") (class "Default")
      (node (ref "Q1") (pin "3") (pinfunction "D_3") (pintype "passive"))
      (node (ref "R4") (pin "2") (pinfunction "2_2") (pintype "passive"))
    )
    (net (code "64") (name "Net-(Q2-D)") (class "Default")
      (node (ref "Q2") (pin "3") (pinfunction "D_3") (pintype "passive"))
      (node (ref "R5") (pin "2") (pinfunction "2_2") (pintype "passive"))
    )
    (net (code "65") (name "Net-(Q3-D)") (class "Default")
      (node (ref "Q3") (pin "3") (pinfunction "D_3") (pintype "passive"))
      (node (ref "R6") (pin "2") (pinfunction "2_2") (pintype "passive"))
    )
    (net (code "66") (name "Net-(Q4-D)") (class "Default")
      (node (ref "Q4") (pin "3") (pinfunction "D_3") (pintype "passive"))
      (node (ref "R10") (pin "2") (pinfunction "2_2") (pintype "passive"))
    )
    (net (code "67") (name "Net-(Q5-D)") (class "Default")
      (node (ref "Q5") (pin "3") (pinfunction "D_3") (pintype "passive"))
      (node (ref "R11") (pin "2") (pinfunction "2_2") (pintype "passive"))
    )
    (net (code "68") (name "Net-(Q6-D)") (class "Default")
      (node (ref "Q6") (pin "3") (pinfunction "D_3") (pintype "passive"))
      (node (ref "R12") (pin "2") (pinfunction "2_2") (pintype "passive"))
    )
    (net (code "69") (name "Net-(Q7-D)") (class "Default")
      (node (ref "Q7") (pin "3") (pinfunction "D_3") (pintype "passive"))
      (node (ref "R7") (pin "2") (pinfunction "2_2") (pintype "passive"))
    )
    (net (code "70") (name "Net-(Q8-D)") (class "Default")
      (node (ref "Q8") (pin "3") (pinfunction "D_3") (pintype "passive"))
      (node (ref "R8") (pin "2") (pinfunction "2_2") (pintype "passive"))
    )
    (net (code "71") (name "Net-(Q9-D)") (class "Default")
      (node (ref "Q9") (pin "3") (pinfunction "D_3") (pintype "passive"))
      (node (ref "R9") (pin "2") (pinfunction "2_2") (pintype "passive"))
    )
    (net (code "72") (name "Net-(Q10-D)") (class "Default")
      (node (ref "Q10") (pin "3") (pinfunction "D_3") (pintype "passive"))
      (node (ref "R13") (pin "2") (pinfunction "2_2") (pintype "passive"))
    )
    (net (code "73") (name "Net-(Q11-D)") (class "Default")
      (node (ref "Q11") (pin "3") (pinfunction "D_3") (pintype "passive"))
      (node (ref "R14") (pin "2") (pinfunction "2_2") (pintype "passive"))
    )
    (net (code "74") (name "Net-(Q12-D)") (class "Default")
      (node (ref "Q12") (pin "3") (pinfunction "D_3") (pintype "passive"))
      (node (ref "R15") (pin "2") (pinfunction "2_2") (pintype "passive"))
    )
    (net (code "75") (name "Net-(Q13-D)") (class "Default")
      (node (ref "Q13") (pin "3") (pinfunction "D_3") (pintype "passive"))
      (node (ref "R19") (pin "2") (pinfunction "2_2") (pintype "passive"))
    )
    (net (code "76") (name "Net-(Q14-D)") (class "Default")
      (node (ref "Q14") (pin "3") (pinfunction "D_3") (pintype "passive"))
      (node (ref "R20") (pin "2") (pinfunction "2_2") (pintype "passive"))
    )
    (net (code "77") (name "Net-(Q15-D)") (class "Default")
      (node (ref "Q15") (pin "3") (pinfunction "D_3") (pintype "passive"))
      (node (ref "R21") (pin "2") (pinfunction "2_2") (pintype "passive"))
    )
    (net (code "78") (name "Net-(Q16-D)") (class "Default")
      (node (ref "Q16") (pin "3") (pinfunction "D_3") (pintype "passive"))
      (node (ref "R16") (pin "2") (pinfunction "2_2") (pintype "passive"))
    )
    (net (code "79") (name "Net-(Q17-D)") (class "Default")
      (node (ref "Q17") (pin "3") (pinfunction "D_3") (pintype "passive"))
      (node (ref "R17") (pin "2") (pinfunction "2_2") (pintype "passive"))
    )
    (net (code "80") (name "Net-(Q18-D)") (class "Default")
      (node (ref "Q18") (pin "3") (pinfunction "D_3") (pintype "passive"))
      (node (ref "R18") (pin "2") (pinfunction "2_2") (pintype "passive"))
    )
    (net (code "81") (name "Net-(Q19-D)") (class "Default")
      (node (ref "Q19") (pin "3") (pinfunction "D_3") (pintype "passive"))
      (node (ref "R22") (pin "2") (pinfunction "2_2") (pintype "passive"))
    )
    (net (code "82") (name "Net-(Q20-D)") (class "Default")
      (node (ref "Q20") (pin "3") (pinfunction "D_3") (pintype "passive"))
      (node (ref "R23") (pin "2") (pinfunction "2_2") (pintype "passive"))
    )
    (net (code "83") (name "Net-(Q21-D)") (class "Default")
      (node (ref "Q21") (pin "3") (pinfunction "D_3") (pintype "passive"))
      (node (ref "R24") (pin "2") (pinfunction "2_2") (pintype "passive"))
    )
    (net (code "84") (name "Net-(Q22-D)") (class "Default")
      (node (ref "Q22") (pin "3") (pinfunction "D_3") (pintype "passive"))
      (node (ref "R28") (pin "2") (pinfunction "2_2") (pintype "passive"))
    )
    (net (code "85") (name "Net-(Q23-D)") (class "Default")
      (node (ref "Q23") (pin "3") (pinfunction "D_3") (pintype "passive"))
      (node (ref "R29") (pin "2") (pinfunction "2_2") (pintype "passive"))
    )
    (net (code "86") (name "Net-(Q24-D)") (class "Default")
      (node (ref "Q24") (pin "3") (pinfunction "D_3") (pintype "passive"))
      (node (ref "R30") (pin "2") (pinfunction "2_2") (pintype "passive"))
    )
    (net (code "87") (name "Net-(Q25-D)") (class "Default")
      (node (ref "Q25") (pin "3") (pinfunction "D_3") (pintype "passive"))
      (node (ref "R25") (pin "2") (pinfunction "2_2") (pintype "passive"))
    )
    (net (code "88") (name "Net-(Q26-D)") (class "Default")
      (node (ref "Q26") (pin "3") (pinfunction "D_3") (pintype "passive"))
      (node (ref "R26") (pin "2") (pinfunction "2_2") (pintype "passive"))
    )
    (net (code "89") (name "Net-(Q27-D)") (class "Default")
      (node (ref "Q27") (pin "3") (pinfunction "D_3") (pintype "passive"))
      (node (ref "R27") (pin "2") (pinfunction "2_2") (pintype "passive"))
    )
    (net (code "90") (name "Net-(Q28-D)") (class "Default")
      (node (ref "Q28") (pin "3") (pinfunction "D_3") (pintype "passive"))
      (node (ref "R31") (pin "2") (pinfunction "2_2") (pintype "passive"))
    )
    (net (code "91") (name "Net-(Q29-D)") (class "Default")
      (node (ref "Q29") (pin "3") (pinfunction "D_3") (pintype "passive"))
      (node (ref "R33") (pin "2") (pinfunction "2_2") (pintype "passive"))
    )
    (net (code "92") (name "Net-(Q30-D)") (class "Default")
      (node (ref "Q30") (pin "3") (pinfunction "D_3") (pintype "passive"))
      (node (ref "R32") (pin "2") (pinfunction "2_2") (pintype "passive"))
    )
  )
)
